# Schematic.net
KiCad netlist of a schematic drawn in Altium Designer
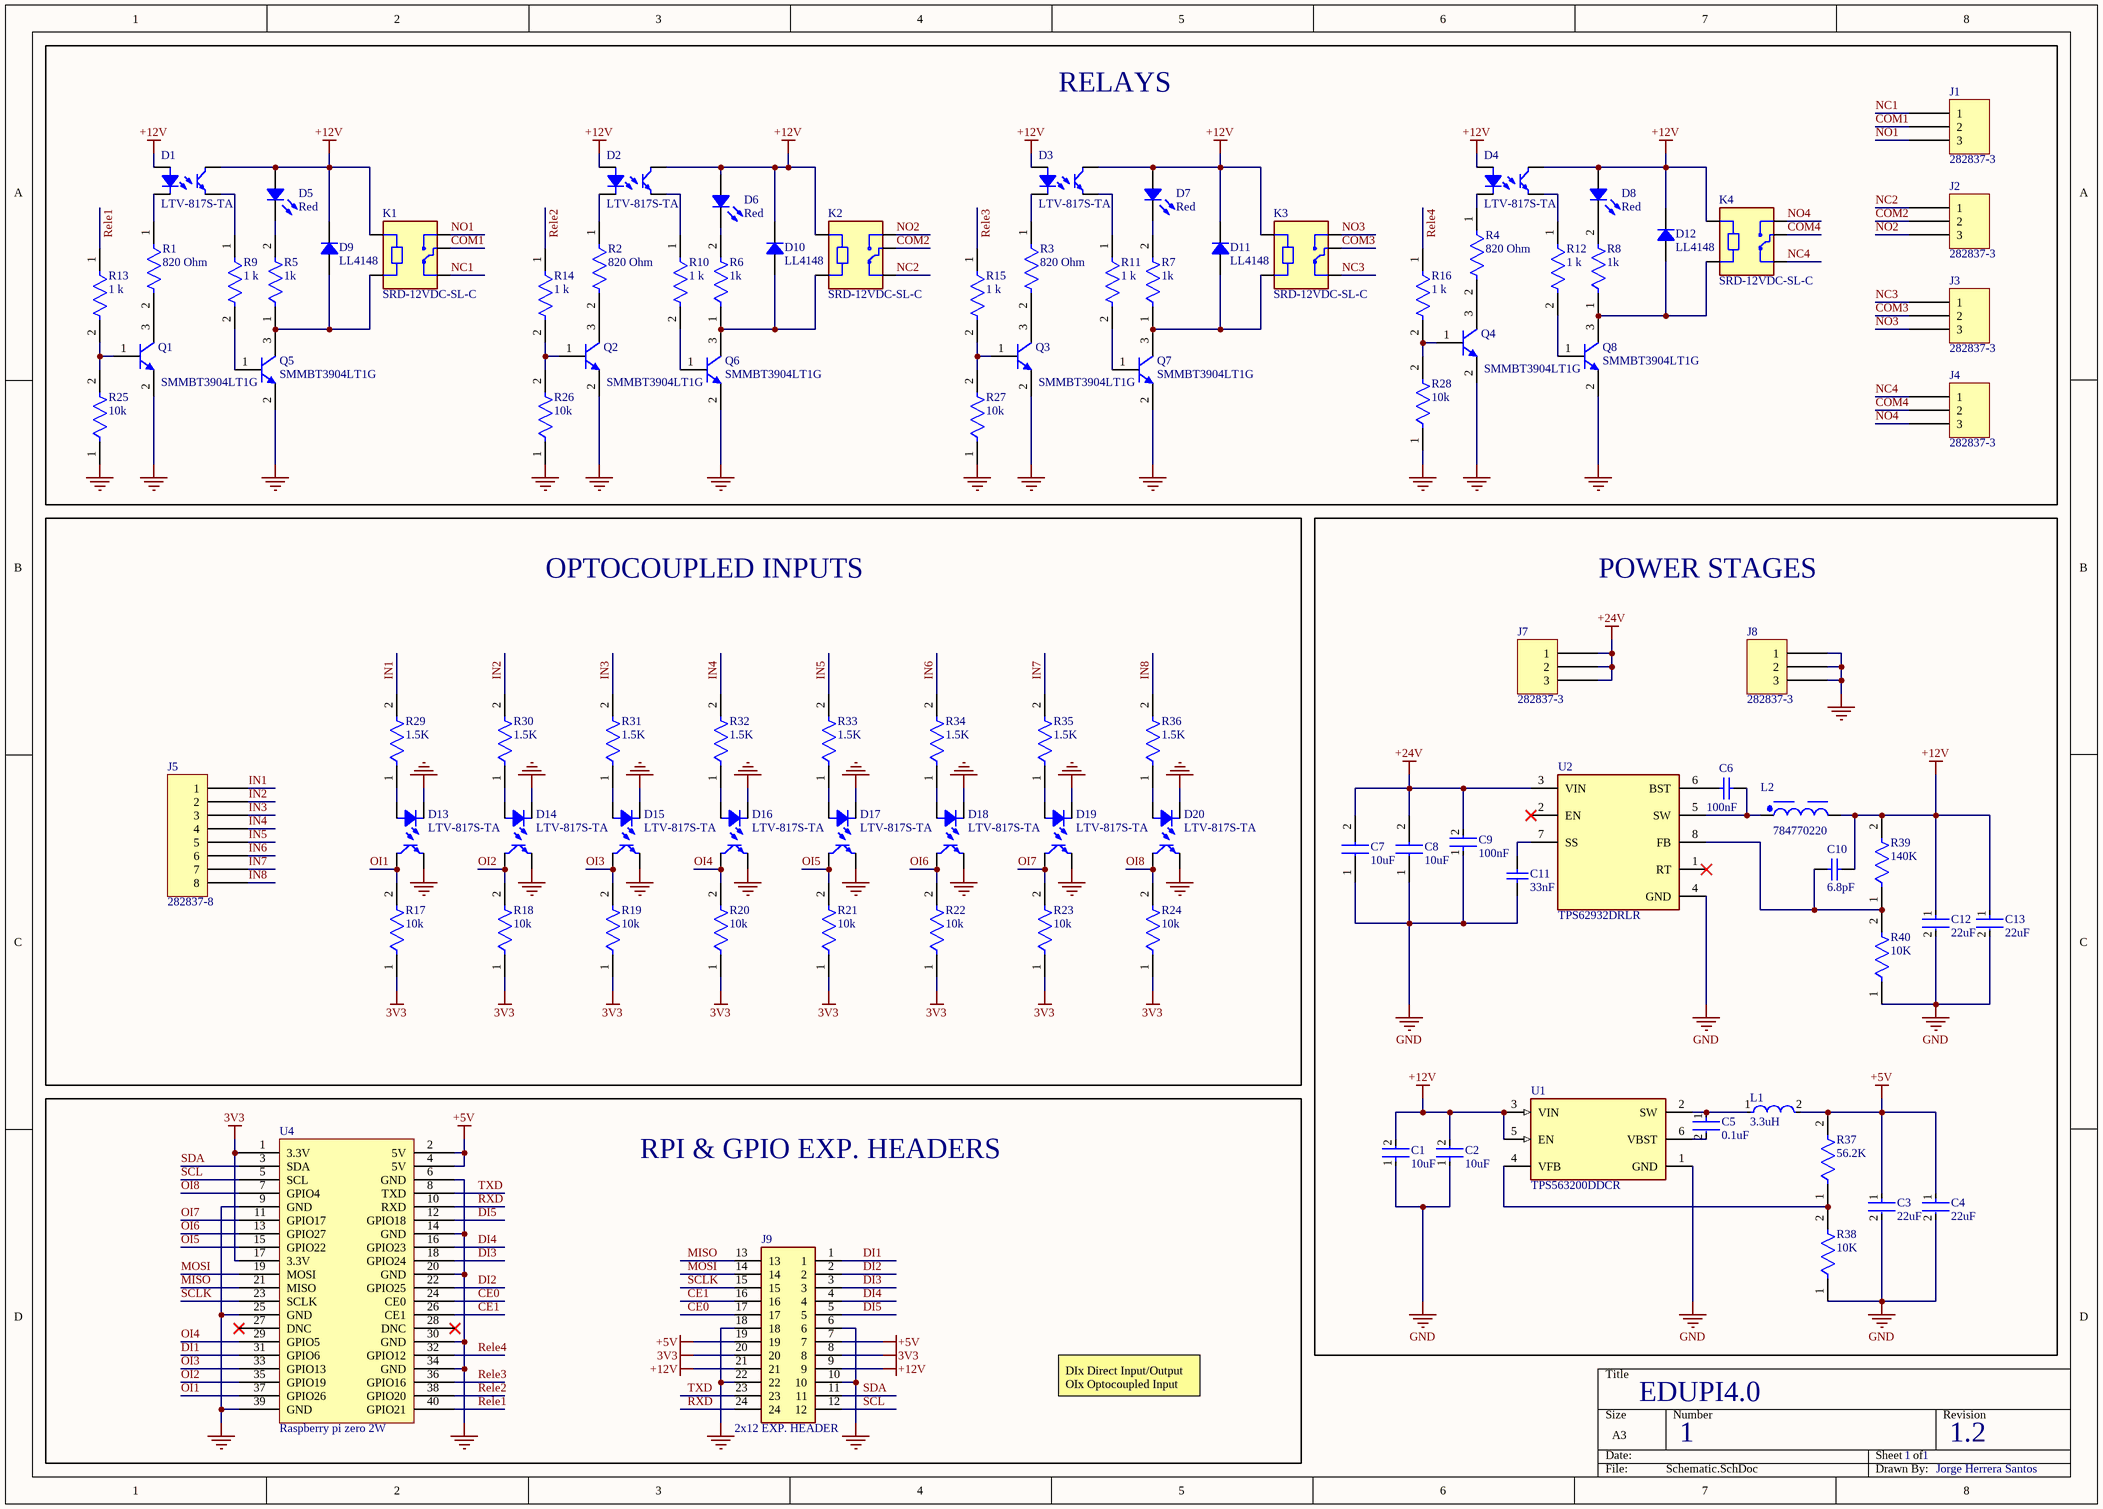
[diagram p0: Schematic.SchDoc]

(export (version "E")
  (design (tool "Eeschema 10.0.6"))
  (components
    (comp (ref "C1")
      (value "10uF")
      (footprint "FP-GRM21B-0_15-IPC_C")
      (description "Chip Multilayer Ceramic Capacitors for General Purpose, 0805, 10uF, X5R, 15%, 10%, 25V")
      (fields (field (name "VOLTAGE") "25V") (field (name "TOLERANCE") "10%"))
      (libsource (lib "Altium Content Vault") (part "b4654b650e69147ec39a6b967a45e02"))
    )
    (comp (ref "C2")
      (value "10uF")
      (footprint "FP-GRM21B-0_15-IPC_C")
      (description "Chip Multilayer Ceramic Capacitors for General Purpose, 0805, 10uF, X5R, 15%, 10%, 25V")
      (fields (field (name "VOLTAGE") "25V") (field (name "TOLERANCE") "10%"))
      (libsource (lib "Altium Content Vault") (part "b4654b650e69147ec39a6b967a45e02"))
    )
    (comp (ref "C3")
      (value "22uF")
      (footprint "FP-GRM21B-0_2-e0_2_0_7-IPC_C")
      (description "Chip Multilayer Ceramic Capacitors for General Purpose, 0805, 22uF, X5R, 15%, 20%, 10V")
      (fields (field (name "TOLERANCE") "20%") (field (name "VOLTAGE") "10V"))
      (libsource (lib "Altium Content Vault") (part "b4654b650e69147ec39a6b967a45e02"))
    )
    (comp (ref "C4")
      (value "22uF")
      (footprint "FP-GRM21B-0_2-e0_2_0_7-IPC_C")
      (description "Chip Multilayer Ceramic Capacitors for General Purpose, 0805, 22uF, X5R, 15%, 20%, 10V")
      (fields (field (name "TOLERANCE") "20%") (field (name "VOLTAGE") "10V"))
      (libsource (lib "Altium Content Vault") (part "b4654b650e69147ec39a6b967a45e02"))
    )
    (comp (ref "C5")
      (value "0.1uF")
      (footprint "FP-CC0805-0_85-MFG")
      (description "CAP CER 0.1UF 25V X7R 0805")
      (fields (field (name "MANUFACTURER PART NUMBER") "CC0805KRX7R8BB104") (field (name "TOLERANCE") "0.1"))
      (libsource (lib "Altium Content Vault") (part "11868f565c42a9108669ba33697ecf6"))
    )
    (comp (ref "C6")
      (value "100nF")
      (footprint "CAPC1005X55X25LL05T10")
      (description "Chip Capacitor, 0.1 uF, +/- 10%, 10 V, -55 to 125 degC, 0402 (1005 Metric), RoHS, Tape and Reel")
      (fields (field (name "MANUFACTURER") "Murata"))
      (libsource (lib "Altium Content Vault") (part "CAP-NP-2"))
    )
    (comp (ref "C7")
      (value "10uF")
      (footprint "CAPC3225X270N")
      (description "Capacitor")
      (fields (field (name "MANUFACTURER_PART_NUMBER") "MSASU32MSB5106KPNA01"))
      (libsource (lib "Raspberry") (part "MSASU32MSB5106KPNA01"))
    )
    (comp (ref "C8")
      (value "10uF")
      (footprint "CAPC3225X270N")
      (description "Capacitor")
      (fields (field (name "MANUFACTURER_PART_NUMBER") "MSASU32MSB5106KPNA01"))
      (libsource (lib "Raspberry") (part "MSASU32MSB5106KPNA01"))
    )
    (comp (ref "C9")
      (value "100nF")
      (footprint "FP-CGA3E-0_3-0_1-IPC_A")
      (description "Cap Ceramic 100nF 50V X7R 10% Pad SMD 0603 +125°C Automotive T/R")
      (fields (field (name "TOLERANCE") "10%") (field (name "VOLTAGE") "50V"))
      (libsource (lib "Altium Content Vault") (part "b4654b650e69147ec39a6b967a45e02"))
    )
    (comp (ref "C10")
      (value "6.8pF")
      (footprint "CAPC1005X55X25NL05T10")
      (fields (field (name "PART NUMBER") "GRM1555C1E6R8CA01D") (field (name "MANUFACTURER") "Murata"))
      (libsource (lib "Altium Content Vault") (part "CAP"))
    )
    (comp (ref "C11")
      (value "33nF")
      (footprint "CAPC1005X55X25NL05T10")
      (fields (field (name "PART NUMBER") "GRM155R71A333KA01D") (field (name "MANUFACTURER") "Murata"))
      (libsource (lib "Altium Content Vault") (part "CAP"))
    )
    (comp (ref "C12")
      (value "22uF")
      (footprint "FP-C3216-160-0_2-IPC_B")
      (description "Multilayer Ceramic Capacitors 22uF ±20% 35V X5R SMD 1206")
      (fields (field (name "TOLERANCE") "20%") (field (name "VOLTAGE") "35V"))
      (libsource (lib "Altium Content Vault") (part "11868f565c42a9108669ba33697ecf6"))
    )
    (comp (ref "C13")
      (value "22uF")
      (footprint "FP-C3216-160-0_2-IPC_B")
      (description "Multilayer Ceramic Capacitors 22uF ±20% 35V X5R SMD 1206")
      (fields (field (name "TOLERANCE") "20%") (field (name "VOLTAGE") "35V"))
      (libsource (lib "Altium Content Vault") (part "11868f565c42a9108669ba33697ecf6"))
    )
    (comp (ref "D1")
      (value "LTV-817S-TA")
      (footprint "LITEON LTV-817")
      (description "OPTOISOLATR 5KV TRANSISTOR 4-SMD")
      (fields (field (name "MANUFACTURER") "Lite-On Inc."))
      (libsource (lib "Celestial Altium Library - altium_library") (part "Optoisolator"))
    )
    (comp (ref "D2")
      (value "LTV-817S-TA")
      (footprint "LITEON LTV-817")
      (description "OPTOISOLATR 5KV TRANSISTOR 4-SMD")
      (fields (field (name "MANUFACTURER") "Lite-On Inc."))
      (libsource (lib "Celestial Altium Library - altium_library") (part "Optoisolator"))
    )
    (comp (ref "D3")
      (value "LTV-817S-TA")
      (footprint "LITEON LTV-817")
      (description "OPTOISOLATR 5KV TRANSISTOR 4-SMD")
      (fields (field (name "MANUFACTURER") "Lite-On Inc."))
      (libsource (lib "Celestial Altium Library - altium_library") (part "Optoisolator"))
    )
    (comp (ref "D4")
      (value "LTV-817S-TA")
      (footprint "LITEON LTV-817")
      (description "OPTOISOLATR 5KV TRANSISTOR 4-SMD")
      (fields (field (name "MANUFACTURER") "Lite-On Inc."))
      (libsource (lib "Celestial Altium Library - altium_library") (part "Optoisolator"))
    )
    (comp (ref "D5")
      (value "Red")
      (footprint "LED 1206_3216 RED")
      (description "LED RED CLEAR SMD")
      (fields (field (name "PART NUMBER") "LTST-C150KAKT") (field (name "MANUFACTURER") "Lite-On Inc."))
      (libsource (lib "Celestial Altium Library - altium_library") (part "LED"))
    )
    (comp (ref "D6")
      (value "Red")
      (footprint "LED 1206_3216 RED")
      (description "LED RED CLEAR SMD")
      (fields (field (name "PART NUMBER") "LTST-C150KAKT") (field (name "MANUFACTURER") "Lite-On Inc."))
      (libsource (lib "Celestial Altium Library - altium_library") (part "LED"))
    )
    (comp (ref "D7")
      (value "Red")
      (footprint "LED 1206_3216 RED")
      (description "LED RED CLEAR SMD")
      (fields (field (name "PART NUMBER") "LTST-C150KAKT") (field (name "MANUFACTURER") "Lite-On Inc."))
      (libsource (lib "Celestial Altium Library - altium_library") (part "LED"))
    )
    (comp (ref "D8")
      (value "Red")
      (footprint "LED 1206_3216 RED")
      (description "LED RED CLEAR SMD")
      (fields (field (name "PART NUMBER") "LTST-C150KAKT") (field (name "MANUFACTURER") "Lite-On Inc."))
      (libsource (lib "Celestial Altium Library - altium_library") (part "LED"))
    )
    (comp (ref "D9")
      (value "LL4148")
      (footprint "SOD-80 MiniMELF")
      (description "DIODE GEN PURP 100V 200MA SOD80")
      (fields (field (name "MANUFACTURER") "ON Semiconductor"))
      (libsource (lib "Celestial Altium Library - altium_library") (part "Diode"))
    )
    (comp (ref "D10")
      (value "LL4148")
      (footprint "SOD-80 MiniMELF")
      (description "DIODE GEN PURP 100V 200MA SOD80")
      (fields (field (name "MANUFACTURER") "ON Semiconductor"))
      (libsource (lib "Celestial Altium Library - altium_library") (part "Diode"))
    )
    (comp (ref "D11")
      (value "LL4148")
      (footprint "SOD-80 MiniMELF")
      (description "DIODE GEN PURP 100V 200MA SOD80")
      (fields (field (name "MANUFACTURER") "ON Semiconductor"))
      (libsource (lib "Celestial Altium Library - altium_library") (part "Diode"))
    )
    (comp (ref "D12")
      (value "LL4148")
      (footprint "SOD-80 MiniMELF")
      (description "DIODE GEN PURP 100V 200MA SOD80")
      (fields (field (name "MANUFACTURER") "ON Semiconductor"))
      (libsource (lib "Celestial Altium Library - altium_library") (part "Diode"))
    )
    (comp (ref "D13")
      (value "LTV-817S-TA")
      (footprint "LITEON LTV-817")
      (description "OPTOISOLATR 5KV TRANSISTOR 4-SMD")
      (fields (field (name "MANUFACTURER") "Lite-On Inc."))
      (libsource (lib "Celestial Altium Library - altium_library") (part "Optoisolator"))
    )
    (comp (ref "D14")
      (value "LTV-817S-TA")
      (footprint "LITEON LTV-817")
      (description "OPTOISOLATR 5KV TRANSISTOR 4-SMD")
      (fields (field (name "MANUFACTURER") "Lite-On Inc."))
      (libsource (lib "Celestial Altium Library - altium_library") (part "Optoisolator"))
    )
    (comp (ref "D15")
      (value "LTV-817S-TA")
      (footprint "LITEON LTV-817")
      (description "OPTOISOLATR 5KV TRANSISTOR 4-SMD")
      (fields (field (name "MANUFACTURER") "Lite-On Inc."))
      (libsource (lib "Celestial Altium Library - altium_library") (part "Optoisolator"))
    )
    (comp (ref "D16")
      (value "LTV-817S-TA")
      (footprint "LITEON LTV-817")
      (description "OPTOISOLATR 5KV TRANSISTOR 4-SMD")
      (fields (field (name "MANUFACTURER") "Lite-On Inc."))
      (libsource (lib "Celestial Altium Library - altium_library") (part "Optoisolator"))
    )
    (comp (ref "D17")
      (value "LTV-817S-TA")
      (footprint "LITEON LTV-817")
      (description "OPTOISOLATR 5KV TRANSISTOR 4-SMD")
      (fields (field (name "MANUFACTURER") "Lite-On Inc."))
      (libsource (lib "Celestial Altium Library - altium_library") (part "Optoisolator"))
    )
    (comp (ref "D18")
      (value "LTV-817S-TA")
      (footprint "LITEON LTV-817")
      (description "OPTOISOLATR 5KV TRANSISTOR 4-SMD")
      (fields (field (name "MANUFACTURER") "Lite-On Inc."))
      (libsource (lib "Celestial Altium Library - altium_library") (part "Optoisolator"))
    )
    (comp (ref "D19")
      (value "LTV-817S-TA")
      (footprint "LITEON LTV-817")
      (description "OPTOISOLATR 5KV TRANSISTOR 4-SMD")
      (fields (field (name "MANUFACTURER") "Lite-On Inc."))
      (libsource (lib "Celestial Altium Library - altium_library") (part "Optoisolator"))
    )
    (comp (ref "D20")
      (value "LTV-817S-TA")
      (footprint "LITEON LTV-817")
      (description "OPTOISOLATR 5KV TRANSISTOR 4-SMD")
      (fields (field (name "MANUFACTURER") "Lite-On Inc."))
      (libsource (lib "Celestial Altium Library - altium_library") (part "Optoisolator"))
    )
    (comp (ref "J1")
      (value "282837-3")
      (footprint "TE 282837-3")
      (description "TERM BLK 3P SIDE ENT 5.08MM PCB")
      (fields (field (name "MANUFACTURER") "TE Connectivity AMP Connectors") (field (name "VOLTAGE") "300 V"))
      (libsource (lib "Celestial Altium Library - altium_library") (part "3 Pin"))
    )
    (comp (ref "J2")
      (value "282837-3")
      (footprint "TE 282837-3")
      (description "TERM BLK 3P SIDE ENT 5.08MM PCB")
      (fields (field (name "MANUFACTURER") "TE Connectivity AMP Connectors") (field (name "VOLTAGE") "300 V"))
      (libsource (lib "Celestial Altium Library - altium_library") (part "3 Pin"))
    )
    (comp (ref "J3")
      (value "282837-3")
      (footprint "TE 282837-3")
      (description "TERM BLK 3P SIDE ENT 5.08MM PCB")
      (fields (field (name "MANUFACTURER") "TE Connectivity AMP Connectors") (field (name "VOLTAGE") "300 V"))
      (libsource (lib "Celestial Altium Library - altium_library") (part "3 Pin"))
    )
    (comp (ref "J4")
      (value "282837-3")
      (footprint "TE 282837-3")
      (description "TERM BLK 3P SIDE ENT 5.08MM PCB")
      (fields (field (name "MANUFACTURER") "TE Connectivity AMP Connectors") (field (name "VOLTAGE") "300 V"))
      (libsource (lib "Celestial Altium Library - altium_library") (part "3 Pin"))
    )
    (comp (ref "J5")
      (value "282837-8")
      (footprint "TE 282837-8")
      (description "TERM BLK 8P SIDE ENT 5.08MM PCB")
      (fields (field (name "MANUFACTURER") "TE Connectivity AMP Connectors") (field (name "VOLTAGE") "300 V"))
      (libsource (lib "Celestial Altium Library - altium_library") (part "8 Pin"))
    )
    (comp (ref "J7")
      (value "282837-3")
      (footprint "TE 282837-3")
      (description "TERM BLK 3P SIDE ENT 5.08MM PCB")
      (fields (field (name "MANUFACTURER") "TE Connectivity AMP Connectors") (field (name "VOLTAGE") "300 V"))
      (libsource (lib "") (part "3 Pin_1"))
    )
    (comp (ref "J8")
      (value "282837-3")
      (footprint "TE 282837-3")
      (description "TERM BLK 3P SIDE ENT 5.08MM PCB")
      (fields (field (name "MANUFACTURER") "TE Connectivity AMP Connectors") (field (name "VOLTAGE") "300 V"))
      (libsource (lib "") (part "3 Pin_1"))
    )
    (comp (ref "J9")
      (value "2x12 EXP. HEADER")
      (footprint "2x12 MALE HEADER")
      (description "Conn Unshrouded Header HDR 20 POS 2.54mm Solder ST Thru-Hole Box")
      (fields (field (name "MF") "TE Connectivity") (field (name "MP") "1-826656-0"))
      (libsource (lib "1-826656-0") (part "2X12 MALE HEADER_1"))
    )
    (comp (ref "K1")
      (value "SRD-12VDC-SL-C")
      (footprint "RELAY_SRD-05VDC-SL-C")
      (fields (field (name "MF") "Songle Relay") (field (name "MP") "SRD-05VDC-SL-C"))
      (libsource (lib "SRD-05VDC-SL-C") (part "SRD-05VDC-SL-C"))
    )
    (comp (ref "K2")
      (value "SRD-12VDC-SL-C")
      (footprint "RELAY_SRD-05VDC-SL-C")
      (fields (field (name "MF") "Songle Relay") (field (name "MP") "SRD-05VDC-SL-C"))
      (libsource (lib "SRD-05VDC-SL-C") (part "SRD-05VDC-SL-C"))
    )
    (comp (ref "K3")
      (value "SRD-12VDC-SL-C")
      (footprint "RELAY_SRD-05VDC-SL-C")
      (fields (field (name "MF") "Songle Relay") (field (name "MP") "SRD-05VDC-SL-C"))
      (libsource (lib "SRD-05VDC-SL-C") (part "SRD-05VDC-SL-C"))
    )
    (comp (ref "K4")
      (value "SRD-12VDC-SL-C")
      (footprint "RELAY_SRD-05VDC-SL-C")
      (fields (field (name "MF") "Songle Relay") (field (name "MP") "SRD-05VDC-SL-C"))
      (libsource (lib "SRD-05VDC-SL-C") (part "SRD-05VDC-SL-C"))
    )
    (comp (ref "L1")
      (value "3.3uH")
      (footprint "FP-NR8040-H_4_2-MFG")
      (description "Shielded Wirewound Inductor 3.3uH 30% 6A 19.5mΩ SMD NRS8040T3R3NJGJ")
      (libsource (lib "Altium Content Vault") (part "725321dda6339637d4d059423bc1c3c"))
    )
    (comp (ref "L2")
      (value "784770220")
      (footprint "WE-PDA_1280")
      (description "Power Inductor, 22Uh, Shielded, 4A Rohs Compliant: Yes")
      (fields (field (name "TOLERANCE") "20%"))
      (libsource (lib "Altium Content Vault") (part "Inductor - 2"))
    )
    (comp (ref "Q1")
      (value "SMMBT3904LT1G")
      (footprint "ONSC-SOT-23-3-318-08_V")
      (description "General Purpose Transistor, NPN Silicon, 3-Pin SOT-23, Pb-Free, Tape and Reel")
      (fields (field (name "MANUFACTURER") "On Semiconductor"))
      (libsource (lib "Altium Content Vault") (part "ONSC-NPN-B1E2C3-3"))
    )
    (comp (ref "Q2")
      (value "SMMBT3904LT1G")
      (footprint "ONSC-SOT-23-3-318-08_V")
      (description "General Purpose Transistor, NPN Silicon, 3-Pin SOT-23, Pb-Free, Tape and Reel")
      (fields (field (name "MANUFACTURER") "On Semiconductor"))
      (libsource (lib "Altium Content Vault") (part "ONSC-NPN-B1E2C3-3"))
    )
    (comp (ref "Q3")
      (value "SMMBT3904LT1G")
      (footprint "ONSC-SOT-23-3-318-08_V")
      (description "General Purpose Transistor, NPN Silicon, 3-Pin SOT-23, Pb-Free, Tape and Reel")
      (fields (field (name "MANUFACTURER") "On Semiconductor"))
      (libsource (lib "Altium Content Vault") (part "ONSC-NPN-B1E2C3-3"))
    )
    (comp (ref "Q4")
      (value "SMMBT3904LT1G")
      (footprint "ONSC-SOT-23-3-318-08_V")
      (description "General Purpose Transistor, NPN Silicon, 3-Pin SOT-23, Pb-Free, Tape and Reel")
      (fields (field (name "MANUFACTURER") "On Semiconductor"))
      (libsource (lib "Altium Content Vault") (part "ONSC-NPN-B1E2C3-3"))
    )
    (comp (ref "Q5")
      (value "SMMBT3904LT1G")
      (footprint "ONSC-SOT-23-3-318-08_V")
      (description "General Purpose Transistor, NPN Silicon, 3-Pin SOT-23, Pb-Free, Tape and Reel")
      (fields (field (name "MANUFACTURER") "On Semiconductor"))
      (libsource (lib "Altium Content Vault") (part "ONSC-NPN-B1E2C3-3"))
    )
    (comp (ref "Q6")
      (value "SMMBT3904LT1G")
      (footprint "ONSC-SOT-23-3-318-08_V")
      (description "General Purpose Transistor, NPN Silicon, 3-Pin SOT-23, Pb-Free, Tape and Reel")
      (fields (field (name "MANUFACTURER") "On Semiconductor"))
      (libsource (lib "Altium Content Vault") (part "ONSC-NPN-B1E2C3-3"))
    )
    (comp (ref "Q7")
      (value "SMMBT3904LT1G")
      (footprint "ONSC-SOT-23-3-318-08_V")
      (description "General Purpose Transistor, NPN Silicon, 3-Pin SOT-23, Pb-Free, Tape and Reel")
      (fields (field (name "MANUFACTURER") "On Semiconductor"))
      (libsource (lib "Altium Content Vault") (part "ONSC-NPN-B1E2C3-3"))
    )
    (comp (ref "Q8")
      (value "SMMBT3904LT1G")
      (footprint "ONSC-SOT-23-3-318-08_V")
      (description "General Purpose Transistor, NPN Silicon, 3-Pin SOT-23, Pb-Free, Tape and Reel")
      (fields (field (name "MANUFACTURER") "On Semiconductor"))
      (libsource (lib "Altium Content Vault") (part "ONSC-NPN-B1E2C3-3"))
    )
    (comp (ref "R1")
      (value "820 Ohm")
      (footprint "FP-CRCW0603-HPe3-MFG")
      (description "RES Thick Film, 820Ω, 1%, 0.33W, 100ppm/°C, 0603")
      (fields (field (name "TOLERANCE") "1%"))
      (libsource (lib "Altium Content Vault") (part "1029c3af85768c4190bb7ad29bc67b5"))
    )
    (comp (ref "R2")
      (value "820 Ohm")
      (footprint "FP-CRCW0603-HPe3-MFG")
      (description "RES Thick Film, 820Ω, 1%, 0.33W, 100ppm/°C, 0603")
      (fields (field (name "TOLERANCE") "1%"))
      (libsource (lib "Altium Content Vault") (part "1029c3af85768c4190bb7ad29bc67b5"))
    )
    (comp (ref "R3")
      (value "820 Ohm")
      (footprint "FP-CRCW0603-HPe3-MFG")
      (description "RES Thick Film, 820Ω, 1%, 0.33W, 100ppm/°C, 0603")
      (fields (field (name "TOLERANCE") "1%"))
      (libsource (lib "Altium Content Vault") (part "1029c3af85768c4190bb7ad29bc67b5"))
    )
    (comp (ref "R4")
      (value "820 Ohm")
      (footprint "FP-CRCW0603-HPe3-MFG")
      (description "RES Thick Film, 820Ω, 1%, 0.33W, 100ppm/°C, 0603")
      (fields (field (name "TOLERANCE") "1%"))
      (libsource (lib "Altium Content Vault") (part "1029c3af85768c4190bb7ad29bc67b5"))
    )
    (comp (ref "R5")
      (value "1k")
      (footprint "FP-CRCW0603-HPe3-MFG")
      (description "RES Thick Film, 820Ω, 1%, 0.33W, 100ppm/°C, 0603")
      (fields (field (name "TOLERANCE") "1%"))
      (libsource (lib "Altium Content Vault") (part "1029c3af85768c4190bb7ad29bc67b5"))
    )
    (comp (ref "R6")
      (value "1k")
      (footprint "FP-CRCW0603-HPe3-MFG")
      (description "RES Thick Film, 820Ω, 1%, 0.33W, 100ppm/°C, 0603")
      (fields (field (name "TOLERANCE") "1%"))
      (libsource (lib "Altium Content Vault") (part "1029c3af85768c4190bb7ad29bc67b5"))
    )
    (comp (ref "R7")
      (value "1k")
      (footprint "FP-CRCW0603-HPe3-MFG")
      (description "RES Thick Film, 820Ω, 1%, 0.33W, 100ppm/°C, 0603")
      (fields (field (name "TOLERANCE") "1%"))
      (libsource (lib "Altium Content Vault") (part "1029c3af85768c4190bb7ad29bc67b5"))
    )
    (comp (ref "R8")
      (value "1k")
      (footprint "FP-CRCW0603-HPe3-MFG")
      (description "RES Thick Film, 820Ω, 1%, 0.33W, 100ppm/°C, 0603")
      (fields (field (name "TOLERANCE") "1%"))
      (libsource (lib "Altium Content Vault") (part "1029c3af85768c4190bb7ad29bc67b5"))
    )
    (comp (ref "R9")
      (value "1 k")
      (footprint "FP-MCT0603-IPC_C")
      (description "MCT0603PD1001DP500 RES SMD 100 OHM 1% 1/8W 0603")
      (fields (field (name "TOLERANCE") "0.5%"))
      (libsource (lib "Altium Content Vault") (part "1029c3af85768c4190bb7ad29bc67b5"))
    )
    (comp (ref "R10")
      (value "1 k")
      (footprint "FP-MCT0603-IPC_C")
      (description "MCT0603PD1001DP500 RES SMD 100 OHM 1% 1/8W 0603")
      (fields (field (name "TOLERANCE") "0.5%"))
      (libsource (lib "Altium Content Vault") (part "1029c3af85768c4190bb7ad29bc67b5"))
    )
    (comp (ref "R11")
      (value "1 k")
      (footprint "FP-MCT0603-IPC_C")
      (description "MCT0603PD1001DP500 RES SMD 100 OHM 1% 1/8W 0603")
      (fields (field (name "TOLERANCE") "0.5%"))
      (libsource (lib "Altium Content Vault") (part "1029c3af85768c4190bb7ad29bc67b5"))
    )
    (comp (ref "R12")
      (value "1 k")
      (footprint "FP-MCT0603-IPC_C")
      (description "MCT0603PD1001DP500 RES SMD 100 OHM 1% 1/8W 0603")
      (fields (field (name "TOLERANCE") "0.5%"))
      (libsource (lib "Altium Content Vault") (part "1029c3af85768c4190bb7ad29bc67b5"))
    )
    (comp (ref "R13")
      (value "1 k")
      (footprint "FP-MCT0603-IPC_C")
      (description "MCT0603PD1001DP500 RES SMD 100 OHM 1% 1/8W 0603")
      (fields (field (name "TOLERANCE") "0.5%"))
      (libsource (lib "Altium Content Vault") (part "1029c3af85768c4190bb7ad29bc67b5"))
    )
    (comp (ref "R14")
      (value "1 k")
      (footprint "FP-MCT0603-IPC_C")
      (description "MCT0603PD1001DP500 RES SMD 100 OHM 1% 1/8W 0603")
      (fields (field (name "TOLERANCE") "0.5%"))
      (libsource (lib "Altium Content Vault") (part "1029c3af85768c4190bb7ad29bc67b5"))
    )
    (comp (ref "R15")
      (value "1 k")
      (footprint "FP-MCT0603-IPC_C")
      (description "MCT0603PD1001DP500 RES SMD 100 OHM 1% 1/8W 0603")
      (fields (field (name "TOLERANCE") "0.5%"))
      (libsource (lib "Altium Content Vault") (part "1029c3af85768c4190bb7ad29bc67b5"))
    )
    (comp (ref "R16")
      (value "1 k")
      (footprint "FP-MCT0603-IPC_C")
      (description "MCT0603PD1001DP500 RES SMD 100 OHM 1% 1/8W 0603")
      (fields (field (name "TOLERANCE") "0.5%"))
      (libsource (lib "Altium Content Vault") (part "1029c3af85768c4190bb7ad29bc67b5"))
    )
    (comp (ref "R17")
      (value "10k")
      (footprint "FP-MCT0603-IPC_B")
      (description "MCT0603MD1002BP100 RES SMD 10k OHM 1% 1/8W 0603")
      (fields (field (name "TOLERANCE") "0.1%"))
      (libsource (lib "Altium Content Vault") (part "1029c3af85768c4190bb7ad29bc67b5"))
    )
    (comp (ref "R18")
      (value "10k")
      (footprint "FP-MCT0603-IPC_B")
      (description "MCT0603MD1002BP100 RES SMD 10k OHM 1% 1/8W 0603")
      (fields (field (name "TOLERANCE") "0.1%"))
      (libsource (lib "Altium Content Vault") (part "1029c3af85768c4190bb7ad29bc67b5"))
    )
    (comp (ref "R19")
      (value "10k")
      (footprint "FP-MCT0603-IPC_B")
      (description "MCT0603MD1002BP100 RES SMD 10k OHM 1% 1/8W 0603")
      (fields (field (name "TOLERANCE") "0.1%"))
      (libsource (lib "Altium Content Vault") (part "1029c3af85768c4190bb7ad29bc67b5"))
    )
    (comp (ref "R20")
      (value "10k")
      (footprint "FP-MCT0603-IPC_B")
      (description "MCT0603MD1002BP100 RES SMD 10k OHM 1% 1/8W 0603")
      (fields (field (name "TOLERANCE") "0.1%"))
      (libsource (lib "Altium Content Vault") (part "1029c3af85768c4190bb7ad29bc67b5"))
    )
    (comp (ref "R21")
      (value "10k")
      (footprint "FP-MCT0603-IPC_B")
      (description "MCT0603MD1002BP100 RES SMD 10k OHM 1% 1/8W 0603")
      (fields (field (name "TOLERANCE") "0.1%"))
      (libsource (lib "Altium Content Vault") (part "1029c3af85768c4190bb7ad29bc67b5"))
    )
    (comp (ref "R22")
      (value "10k")
      (footprint "FP-MCT0603-IPC_B")
      (description "MCT0603MD1002BP100 RES SMD 10k OHM 1% 1/8W 0603")
      (fields (field (name "TOLERANCE") "0.1%"))
      (libsource (lib "Altium Content Vault") (part "1029c3af85768c4190bb7ad29bc67b5"))
    )
    (comp (ref "R23")
      (value "10k")
      (footprint "FP-MCT0603-IPC_B")
      (description "MCT0603MD1002BP100 RES SMD 10k OHM 1% 1/8W 0603")
      (fields (field (name "TOLERANCE") "0.1%"))
      (libsource (lib "Altium Content Vault") (part "1029c3af85768c4190bb7ad29bc67b5"))
    )
    (comp (ref "R24")
      (value "10k")
      (footprint "FP-MCT0603-IPC_B")
      (description "MCT0603MD1002BP100 RES SMD 10k OHM 1% 1/8W 0603")
      (fields (field (name "TOLERANCE") "0.1%"))
      (libsource (lib "Altium Content Vault") (part "1029c3af85768c4190bb7ad29bc67b5"))
    )
    (comp (ref "R25")
      (value "10k")
      (footprint "FP-MCT0603-IPC_B")
      (description "MCT0603MD1002BP100 RES SMD 10k OHM 1% 1/8W 0603")
      (fields (field (name "TOLERANCE") "0.1%"))
      (libsource (lib "Altium Content Vault") (part "1029c3af85768c4190bb7ad29bc67b5"))
    )
    (comp (ref "R26")
      (value "10k")
      (footprint "FP-MCT0603-IPC_B")
      (description "MCT0603MD1002BP100 RES SMD 10k OHM 1% 1/8W 0603")
      (fields (field (name "TOLERANCE") "0.1%"))
      (libsource (lib "Altium Content Vault") (part "1029c3af85768c4190bb7ad29bc67b5"))
    )
    (comp (ref "R27")
      (value "10k")
      (footprint "FP-MCT0603-IPC_B")
      (description "MCT0603MD1002BP100 RES SMD 10k OHM 1% 1/8W 0603")
      (fields (field (name "TOLERANCE") "0.1%"))
      (libsource (lib "Altium Content Vault") (part "1029c3af85768c4190bb7ad29bc67b5"))
    )
    (comp (ref "R28")
      (value "10k")
      (footprint "FP-MCT0603-IPC_B")
      (description "MCT0603MD1002BP100 RES SMD 10k OHM 1% 1/8W 0603")
      (fields (field (name "TOLERANCE") "0.1%"))
      (libsource (lib "Altium Content Vault") (part "1029c3af85768c4190bb7ad29bc67b5"))
    )
    (comp (ref "R29")
      (value "1.5K")
      (footprint "FP-CRCW0603-e3-IPC_C")
      (description "CRCW06031K50FKEC RES Thick Film, 1.5kΩ, 1%, 0.1W, 100ppm/°C, 0603")
      (fields (field (name "TOLERANCE") "1%"))
      (libsource (lib "Altium Content Vault") (part "1029c3af85768c4190bb7ad29bc67b5"))
    )
    (comp (ref "R30")
      (value "1.5K")
      (footprint "FP-CRCW0603-e3-IPC_C")
      (description "CRCW06031K50FKEC RES Thick Film, 1.5kΩ, 1%, 0.1W, 100ppm/°C, 0603")
      (fields (field (name "TOLERANCE") "1%"))
      (libsource (lib "Altium Content Vault") (part "1029c3af85768c4190bb7ad29bc67b5"))
    )
    (comp (ref "R31")
      (value "1.5K")
      (footprint "FP-CRCW0603-e3-IPC_C")
      (description "CRCW06031K50FKEC RES Thick Film, 1.5kΩ, 1%, 0.1W, 100ppm/°C, 0603")
      (fields (field (name "TOLERANCE") "1%"))
      (libsource (lib "Altium Content Vault") (part "1029c3af85768c4190bb7ad29bc67b5"))
    )
    (comp (ref "R32")
      (value "1.5K")
      (footprint "FP-CRCW0603-e3-IPC_C")
      (description "CRCW06031K50FKEC RES Thick Film, 1.5kΩ, 1%, 0.1W, 100ppm/°C, 0603")
      (fields (field (name "TOLERANCE") "1%"))
      (libsource (lib "Altium Content Vault") (part "1029c3af85768c4190bb7ad29bc67b5"))
    )
    (comp (ref "R33")
      (value "1.5K")
      (footprint "FP-CRCW0603-e3-IPC_C")
      (description "CRCW06031K50FKEC RES Thick Film, 1.5kΩ, 1%, 0.1W, 100ppm/°C, 0603")
      (fields (field (name "TOLERANCE") "1%"))
      (libsource (lib "Altium Content Vault") (part "1029c3af85768c4190bb7ad29bc67b5"))
    )
    (comp (ref "R34")
      (value "1.5K")
      (footprint "FP-CRCW0603-e3-IPC_C")
      (description "CRCW06031K50FKEC RES Thick Film, 1.5kΩ, 1%, 0.1W, 100ppm/°C, 0603")
      (fields (field (name "TOLERANCE") "1%"))
      (libsource (lib "Altium Content Vault") (part "1029c3af85768c4190bb7ad29bc67b5"))
    )
    (comp (ref "R35")
      (value "1.5K")
      (footprint "FP-CRCW0603-e3-IPC_C")
      (description "CRCW06031K50FKEC RES Thick Film, 1.5kΩ, 1%, 0.1W, 100ppm/°C, 0603")
      (fields (field (name "TOLERANCE") "1%"))
      (libsource (lib "Altium Content Vault") (part "1029c3af85768c4190bb7ad29bc67b5"))
    )
    (comp (ref "R36")
      (value "1.5K")
      (footprint "FP-CRCW0603-e3-IPC_C")
      (description "CRCW06031K50FKEC RES Thick Film, 1.5kΩ, 1%, 0.1W, 100ppm/°C, 0603")
      (fields (field (name "TOLERANCE") "1%"))
      (libsource (lib "Altium Content Vault") (part "1029c3af85768c4190bb7ad29bc67b5"))
    )
    (comp (ref "R37")
      (value "56.2K")
      (footprint "FP-MCT0603-IPC_B")
      (description "RES SMD 100 OHM 1% 1/8W 0603")
      (fields (field (name "TOLERANCE") "1%"))
      (libsource (lib "Altium Content Vault") (part "1029c3af85768c4190bb7ad29bc67b5"))
    )
    (comp (ref "R38")
      (value "10K")
      (footprint "FP-MCT0603-IPC_C")
      (description "RES SMD 10K OHM 1% 1/8W 0603")
      (fields (field (name "TOLERANCE") "1%"))
      (libsource (lib "Altium Content Vault") (part "1029c3af85768c4190bb7ad29bc67b5"))
    )
    (comp (ref "R39")
      (value "140K")
      (footprint "FP-CRCW0603-HPe3-IPC_C")
      (description "RES Thick Film, 140kΩ, 1%, 0.33W, 100ppm/°C, 0603")
      (fields (field (name "TOLERANCE") "1%"))
      (libsource (lib "Altium Content Vault") (part "1029c3af85768c4190bb7ad29bc67b5"))
    )
    (comp (ref "R40")
      (value "10K")
      (footprint "FP-MCT0603-IPC_C")
      (description "RES SMD 10K OHM 1% 1/5W 0603")
      (fields (field (name "TOLERANCE") "1%"))
      (libsource (lib "Altium Content Vault") (part "1029c3af85768c4190bb7ad29bc67b5"))
    )
    (comp (ref "U1")
      (value "TPS563200DDCR")
      (footprint "FP-DDC0006A-MFG")
      (description "IC REG BUCK ADJ 3A TSOT23-6")
      (libsource (lib "Altium Content Vault") (part "31d0a13bcb823f7fa58c78a9b473f81"))
    )
    (comp (ref "U2")
      (value "TPS62932DRLR")
      (footprint "FP-DRL0008A-MFG")
      (description "3.8-V TO 30-V INPUT, 2-A, 200-KH")
      (libsource (lib "Altium Content Vault") (part "530d7937587d685a4b43e131d046c77"))
    )
    (comp (ref "U4")
      (value "Raspberry pi zero 2W")
      (footprint "Raspberry Pi Zero 2 W")
      (libsource (lib "Raspberry") (part "Raspberry pi zero 2W"))
    )
  )
  (nets
    (net (code "1") (name "+5V") (class "Default")
      (node (ref "C3") (pin "1") (pinfunction "1_1") (pintype "passive"))
      (node (ref "C4") (pin "1") (pinfunction "1_1") (pintype "passive"))
      (node (ref "J9") (pin "19") (pinfunction "19_19") (pintype "passive"))
      (node (ref "J9") (pin "7") (pinfunction "7_7") (pintype "passive"))
      (node (ref "L1") (pin "2") (pinfunction "2_2") (pintype "passive"))
      (node (ref "R37") (pin "2") (pinfunction "2_2") (pintype "passive"))
      (node (ref "U4") (pin "2") (pinfunction "5V_2") (pintype "passive"))
      (node (ref "U4") (pin "4") (pinfunction "5V_4") (pintype "passive"))
    )
    (net (code "2") (name "+12V") (class "Default")
      (node (ref "C1") (pin "2") (pinfunction "2_2") (pintype "passive"))
      (node (ref "C10") (pin "2") (pinfunction "2_2") (pintype "passive"))
      (node (ref "C12") (pin "1") (pinfunction "1_1") (pintype "passive"))
      (node (ref "C13") (pin "1") (pinfunction "1_1") (pintype "passive"))
      (node (ref "C2") (pin "2") (pinfunction "2_2") (pintype "passive"))
      (node (ref "D1") (pin "1") (pinfunction "1_1") (pintype "passive"))
      (node (ref "D1") (pin "4") (pinfunction "4_4") (pintype "passive"))
      (node (ref "D10") (pin "2") (pinfunction "2_2") (pintype "passive"))
      (node (ref "D11") (pin "2") (pinfunction "2_2") (pintype "passive"))
      (node (ref "D12") (pin "2") (pinfunction "2_2") (pintype "passive"))
      (node (ref "D2") (pin "1") (pinfunction "1_1") (pintype "passive"))
      (node (ref "D2") (pin "4") (pinfunction "4_4") (pintype "passive"))
      (node (ref "D3") (pin "1") (pinfunction "1_1") (pintype "passive"))
      (node (ref "D3") (pin "4") (pinfunction "4_4") (pintype "passive"))
      (node (ref "D4") (pin "1") (pinfunction "1_1") (pintype "passive"))
      (node (ref "D4") (pin "4") (pinfunction "4_4") (pintype "passive"))
      (node (ref "D5") (pin "1") (pinfunction "1_1") (pintype "passive"))
      (node (ref "D6") (pin "1") (pinfunction "1_1") (pintype "passive"))
      (node (ref "D7") (pin "1") (pinfunction "1_1") (pintype "passive"))
      (node (ref "D8") (pin "1") (pinfunction "1_1") (pintype "passive"))
      (node (ref "D9") (pin "2") (pinfunction "2_2") (pintype "passive"))
      (node (ref "J9") (pin "21") (pinfunction "21_21") (pintype "passive"))
      (node (ref "J9") (pin "9") (pinfunction "9_9") (pintype "passive"))
      (node (ref "K1") (pin "A1") (pinfunction "A1_A1") (pintype "passive"))
      (node (ref "K2") (pin "A1") (pinfunction "A1_A1") (pintype "passive"))
      (node (ref "K3") (pin "A1") (pinfunction "A1_A1") (pintype "passive"))
      (node (ref "K4") (pin "A1") (pinfunction "A1_A1") (pintype "passive"))
      (node (ref "L2") (pin "2") (pinfunction "2_2") (pintype "passive"))
      (node (ref "R39") (pin "2") (pinfunction "2_2") (pintype "passive"))
      (node (ref "U1") (pin "3") (pinfunction "VIN_3") (pintype "input"))
      (node (ref "U1") (pin "5") (pinfunction "EN_5") (pintype "input"))
    )
    (net (code "3") (name "+24V") (class "Default")
      (node (ref "C7") (pin "2") (pinfunction "2_2") (pintype "passive"))
      (node (ref "C8") (pin "2") (pinfunction "2_2") (pintype "passive"))
      (node (ref "C9") (pin "2") (pinfunction "2_2") (pintype "passive"))
      (node (ref "J7") (pin "1") (pinfunction "1_1") (pintype "passive"))
      (node (ref "J7") (pin "2") (pinfunction "2_2") (pintype "passive"))
      (node (ref "J7") (pin "3") (pinfunction "3_3") (pintype "passive"))
      (node (ref "U2") (pin "3") (pinfunction "VIN_3") (pintype "power_in"))
    )
    (net (code "4") (name "/CE0") (class "Default")
      (node (ref "J9") (pin "17") (pinfunction "17_17") (pintype "passive"))
      (node (ref "U4") (pin "24") (pinfunction "CE0_24") (pintype "passive"))
    )
    (net (code "5") (name "/CE1") (class "Default")
      (node (ref "J9") (pin "16") (pinfunction "16_16") (pintype "passive"))
      (node (ref "U4") (pin "26") (pinfunction "CE1_26") (pintype "passive"))
    )
    (net (code "6") (name "/COM1") (class "Default")
      (node (ref "J1") (pin "2") (pinfunction "2_2") (pintype "passive"))
      (node (ref "K1") (pin "COM") (pinfunction "COM_COM") (pintype "passive"))
    )
    (net (code "7") (name "/COM2") (class "Default")
      (node (ref "J2") (pin "2") (pinfunction "2_2") (pintype "passive"))
      (node (ref "K2") (pin "COM") (pinfunction "COM_COM") (pintype "passive"))
    )
    (net (code "8") (name "/COM3") (class "Default")
      (node (ref "J3") (pin "2") (pinfunction "2_2") (pintype "passive"))
      (node (ref "K3") (pin "COM") (pinfunction "COM_COM") (pintype "passive"))
    )
    (net (code "9") (name "/COM4") (class "Default")
      (node (ref "J4") (pin "2") (pinfunction "2_2") (pintype "passive"))
      (node (ref "K4") (pin "COM") (pinfunction "COM_COM") (pintype "passive"))
    )
    (net (code "10") (name "/DI1") (class "Default")
      (node (ref "J9") (pin "1") (pinfunction "1_1") (pintype "passive"))
      (node (ref "U4") (pin "31") (pinfunction "GPIO6_31") (pintype "passive"))
    )
    (net (code "11") (name "/DI2") (class "Default")
      (node (ref "J9") (pin "2") (pinfunction "2_2") (pintype "passive"))
      (node (ref "U4") (pin "22") (pinfunction "GPIO25_22") (pintype "passive"))
    )
    (net (code "12") (name "/DI3") (class "Default")
      (node (ref "J9") (pin "3") (pinfunction "3_3") (pintype "passive"))
      (node (ref "U4") (pin "18") (pinfunction "GPIO24_18") (pintype "passive"))
    )
    (net (code "13") (name "/DI4") (class "Default")
      (node (ref "J9") (pin "4") (pinfunction "4_4") (pintype "passive"))
      (node (ref "U4") (pin "16") (pinfunction "GPIO23_16") (pintype "passive"))
    )
    (net (code "14") (name "/DI5") (class "Default")
      (node (ref "J9") (pin "5") (pinfunction "5_5") (pintype "passive"))
      (node (ref "U4") (pin "12") (pinfunction "GPIO18_12") (pintype "passive"))
    )
    (net (code "15") (name "/IN1") (class "Default")
      (node (ref "J5") (pin "1") (pinfunction "1_1") (pintype "passive"))
      (node (ref "R29") (pin "2") (pinfunction "2_2") (pintype "passive"))
    )
    (net (code "16") (name "/IN2") (class "Default")
      (node (ref "J5") (pin "2") (pinfunction "2_2") (pintype "passive"))
      (node (ref "R30") (pin "2") (pinfunction "2_2") (pintype "passive"))
    )
    (net (code "17") (name "/IN3") (class "Default")
      (node (ref "J5") (pin "3") (pinfunction "3_3") (pintype "passive"))
      (node (ref "R31") (pin "2") (pinfunction "2_2") (pintype "passive"))
    )
    (net (code "18") (name "/IN4") (class "Default")
      (node (ref "J5") (pin "4") (pinfunction "4_4") (pintype "passive"))
      (node (ref "R32") (pin "2") (pinfunction "2_2") (pintype "passive"))
    )
    (net (code "19") (name "/IN5") (class "Default")
      (node (ref "J5") (pin "5") (pinfunction "5_5") (pintype "passive"))
      (node (ref "R33") (pin "2") (pinfunction "2_2") (pintype "passive"))
    )
    (net (code "20") (name "/IN6") (class "Default")
      (node (ref "J5") (pin "6") (pinfunction "6_6") (pintype "passive"))
      (node (ref "R34") (pin "2") (pinfunction "2_2") (pintype "passive"))
    )
    (net (code "21") (name "/IN7") (class "Default")
      (node (ref "J5") (pin "7") (pinfunction "7_7") (pintype "passive"))
      (node (ref "R35") (pin "2") (pinfunction "2_2") (pintype "passive"))
    )
    (net (code "22") (name "/IN8") (class "Default")
      (node (ref "J5") (pin "8") (pinfunction "8_8") (pintype "passive"))
      (node (ref "R36") (pin "2") (pinfunction "2_2") (pintype "passive"))
    )
    (net (code "23") (name "/MISO") (class "Default")
      (node (ref "J9") (pin "13") (pinfunction "13_13") (pintype "passive"))
      (node (ref "U4") (pin "21") (pinfunction "MISO_21") (pintype "passive"))
    )
    (net (code "24") (name "/MOSI") (class "Default")
      (node (ref "J9") (pin "14") (pinfunction "14_14") (pintype "passive"))
      (node (ref "U4") (pin "19") (pinfunction "MOSI_19") (pintype "passive"))
    )
    (net (code "25") (name "/NC1") (class "Default")
      (node (ref "J1") (pin "1") (pinfunction "1_1") (pintype "passive"))
      (node (ref "K1") (pin "NC") (pinfunction "NC_NC") (pintype "passive"))
    )
    (net (code "26") (name "/NC2") (class "Default")
      (node (ref "J2") (pin "1") (pinfunction "1_1") (pintype "passive"))
      (node (ref "K2") (pin "NC") (pinfunction "NC_NC") (pintype "passive"))
    )
    (net (code "27") (name "/NC3") (class "Default")
      (node (ref "J3") (pin "1") (pinfunction "1_1") (pintype "passive"))
      (node (ref "K3") (pin "NC") (pinfunction "NC_NC") (pintype "passive"))
    )
    (net (code "28") (name "/NC4") (class "Default")
      (node (ref "J4") (pin "1") (pinfunction "1_1") (pintype "passive"))
      (node (ref "K4") (pin "NC") (pinfunction "NC_NC") (pintype "passive"))
    )
    (net (code "29") (name "/NO1") (class "Default")
      (node (ref "J1") (pin "3") (pinfunction "3_3") (pintype "passive"))
      (node (ref "K1") (pin "NO") (pinfunction "NO_NO") (pintype "passive"))
    )
    (net (code "30") (name "/NO2") (class "Default")
      (node (ref "J2") (pin "3") (pinfunction "3_3") (pintype "passive"))
      (node (ref "K2") (pin "NO") (pinfunction "NO_NO") (pintype "passive"))
    )
    (net (code "31") (name "/NO3") (class "Default")
      (node (ref "J3") (pin "3") (pinfunction "3_3") (pintype "passive"))
      (node (ref "K3") (pin "NO") (pinfunction "NO_NO") (pintype "passive"))
    )
    (net (code "32") (name "/NO4") (class "Default")
      (node (ref "J4") (pin "3") (pinfunction "3_3") (pintype "passive"))
      (node (ref "K4") (pin "NO") (pinfunction "NO_NO") (pintype "passive"))
    )
    (net (code "33") (name "/OI1") (class "Default")
      (node (ref "D13") (pin "4") (pinfunction "4_4") (pintype "passive"))
      (node (ref "R17") (pin "2") (pinfunction "2_2") (pintype "passive"))
      (node (ref "U4") (pin "37") (pinfunction "GPIO26_37") (pintype "passive"))
    )
    (net (code "34") (name "/OI2") (class "Default")
      (node (ref "D14") (pin "4") (pinfunction "4_4") (pintype "passive"))
      (node (ref "R18") (pin "2") (pinfunction "2_2") (pintype "passive"))
      (node (ref "U4") (pin "35") (pinfunction "GPIO19_35") (pintype "passive"))
    )
    (net (code "35") (name "/OI3") (class "Default")
      (node (ref "D15") (pin "4") (pinfunction "4_4") (pintype "passive"))
      (node (ref "R19") (pin "2") (pinfunction "2_2") (pintype "passive"))
      (node (ref "U4") (pin "33") (pinfunction "GPIO13_33") (pintype "passive"))
    )
    (net (code "36") (name "/OI4") (class "Default")
      (node (ref "D16") (pin "4") (pinfunction "4_4") (pintype "passive"))
      (node (ref "R20") (pin "2") (pinfunction "2_2") (pintype "passive"))
      (node (ref "U4") (pin "29") (pinfunction "GPIO5_29") (pintype "passive"))
    )
    (net (code "37") (name "/OI5") (class "Default")
      (node (ref "D17") (pin "4") (pinfunction "4_4") (pintype "passive"))
      (node (ref "R21") (pin "2") (pinfunction "2_2") (pintype "passive"))
      (node (ref "U4") (pin "15") (pinfunction "GPIO22_15") (pintype "passive"))
    )
    (net (code "38") (name "/OI6") (class "Default")
      (node (ref "D18") (pin "4") (pinfunction "4_4") (pintype "passive"))
      (node (ref "R22") (pin "2") (pinfunction "2_2") (pintype "passive"))
      (node (ref "U4") (pin "13") (pinfunction "GPIO27_13") (pintype "passive"))
    )
    (net (code "39") (name "/OI7") (class "Default")
      (node (ref "D19") (pin "4") (pinfunction "4_4") (pintype "passive"))
      (node (ref "R23") (pin "2") (pinfunction "2_2") (pintype "passive"))
      (node (ref "U4") (pin "11") (pinfunction "GPIO17_11") (pintype "passive"))
    )
    (net (code "40") (name "/OI8") (class "Default")
      (node (ref "D20") (pin "4") (pinfunction "4_4") (pintype "passive"))
      (node (ref "R24") (pin "2") (pinfunction "2_2") (pintype "passive"))
      (node (ref "U4") (pin "7") (pinfunction "GPIO4_7") (pintype "passive"))
    )
    (net (code "41") (name "/RXD") (class "Default")
      (node (ref "J9") (pin "24") (pinfunction "24_24") (pintype "passive"))
      (node (ref "U4") (pin "10") (pinfunction "RXD_10") (pintype "passive"))
    )
    (net (code "42") (name "/Rele1") (class "Default")
      (node (ref "R13") (pin "1") (pinfunction "1_1") (pintype "passive"))
      (node (ref "U4") (pin "40") (pinfunction "GPIO21_40") (pintype "passive"))
    )
    (net (code "43") (name "/Rele2") (class "Default")
      (node (ref "R14") (pin "1") (pinfunction "1_1") (pintype "passive"))
      (node (ref "U4") (pin "38") (pinfunction "GPIO20_38") (pintype "passive"))
    )
    (net (code "44") (name "/Rele3") (class "Default")
      (node (ref "R15") (pin "1") (pinfunction "1_1") (pintype "passive"))
      (node (ref "U4") (pin "36") (pinfunction "GPIO16_36") (pintype "passive"))
    )
    (net (code "45") (name "/Rele4") (class "Default")
      (node (ref "R16") (pin "1") (pinfunction "1_1") (pintype "passive"))
      (node (ref "U4") (pin "32") (pinfunction "GPIO12_32") (pintype "passive"))
    )
    (net (code "46") (name "/SCL") (class "Default")
      (node (ref "J9") (pin "12") (pinfunction "12_12") (pintype "passive"))
      (node (ref "U4") (pin "5") (pinfunction "SCL_5") (pintype "passive"))
    )
    (net (code "47") (name "/SCLK") (class "Default")
      (node (ref "J9") (pin "15") (pinfunction "15_15") (pintype "passive"))
      (node (ref "U4") (pin "23") (pinfunction "SCLK_23") (pintype "passive"))
    )
    (net (code "48") (name "/SDA") (class "Default")
      (node (ref "J9") (pin "11") (pinfunction "11_11") (pintype "passive"))
      (node (ref "U4") (pin "3") (pinfunction "SDA_3") (pintype "passive"))
    )
    (net (code "49") (name "/TXD") (class "Default")
      (node (ref "J9") (pin "23") (pinfunction "23_23") (pintype "passive"))
      (node (ref "U4") (pin "8") (pinfunction "TXD_8") (pintype "passive"))
    )
    (net (code "50") (name "3V3") (class "Default")
      (node (ref "J9") (pin "20") (pinfunction "20_20") (pintype "passive"))
      (node (ref "J9") (pin "8") (pinfunction "8_8") (pintype "passive"))
      (node (ref "R17") (pin "1") (pinfunction "1_1") (pintype "passive"))
      (node (ref "R18") (pin "1") (pinfunction "1_1") (pintype "passive"))
      (node (ref "R19") (pin "1") (pinfunction "1_1") (pintype "passive"))
      (node (ref "R20") (pin "1") (pinfunction "1_1") (pintype "passive"))
      (node (ref "R21") (pin "1") (pinfunction "1_1") (pintype "passive"))
      (node (ref "R22") (pin "1") (pinfunction "1_1") (pintype "passive"))
      (node (ref "R23") (pin "1") (pinfunction "1_1") (pintype "passive"))
      (node (ref "R24") (pin "1") (pinfunction "1_1") (pintype "passive"))
      (node (ref "U4") (pin "1") (pinfunction "3.3V_1") (pintype "passive"))
      (node (ref "U4") (pin "17") (pinfunction "3.3V_17") (pintype "passive"))
    )
    (net (code "51") (name "GND") (class "Default")
      (node (ref "C1") (pin "1") (pinfunction "1_1") (pintype "passive"))
      (node (ref "C11") (pin "1") (pinfunction "1_1") (pintype "passive"))
      (node (ref "C12") (pin "2") (pinfunction "2_2") (pintype "passive"))
      (node (ref "C13") (pin "2") (pinfunction "2_2") (pintype "passive"))
      (node (ref "C2") (pin "1") (pinfunction "1_1") (pintype "passive"))
      (node (ref "C3") (pin "2") (pinfunction "2_2") (pintype "passive"))
      (node (ref "C4") (pin "2") (pinfunction "2_2") (pintype "passive"))
      (node (ref "C7") (pin "1") (pinfunction "1_1") (pintype "passive"))
      (node (ref "C8") (pin "1") (pinfunction "1_1") (pintype "passive"))
      (node (ref "C9") (pin "1") (pinfunction "1_1") (pintype "passive"))
      (node (ref "D13") (pin "2") (pinfunction "2_2") (pintype "passive"))
      (node (ref "D13") (pin "3") (pinfunction "3_3") (pintype "passive"))
      (node (ref "D14") (pin "2") (pinfunction "2_2") (pintype "passive"))
      (node (ref "D14") (pin "3") (pinfunction "3_3") (pintype "passive"))
      (node (ref "D15") (pin "2") (pinfunction "2_2") (pintype "passive"))
      (node (ref "D15") (pin "3") (pinfunction "3_3") (pintype "passive"))
      (node (ref "D16") (pin "2") (pinfunction "2_2") (pintype "passive"))
      (node (ref "D16") (pin "3") (pinfunction "3_3") (pintype "passive"))
      (node (ref "D17") (pin "2") (pinfunction "2_2") (pintype "passive"))
      (node (ref "D17") (pin "3") (pinfunction "3_3") (pintype "passive"))
      (node (ref "D18") (pin "2") (pinfunction "2_2") (pintype "passive"))
      (node (ref "D18") (pin "3") (pinfunction "3_3") (pintype "passive"))
      (node (ref "D19") (pin "2") (pinfunction "2_2") (pintype "passive"))
      (node (ref "D19") (pin "3") (pinfunction "3_3") (pintype "passive"))
      (node (ref "D20") (pin "2") (pinfunction "2_2") (pintype "passive"))
      (node (ref "D20") (pin "3") (pinfunction "3_3") (pintype "passive"))
      (node (ref "J8") (pin "1") (pinfunction "1_1") (pintype "passive"))
      (node (ref "J8") (pin "2") (pinfunction "2_2") (pintype "passive"))
      (node (ref "J8") (pin "3") (pinfunction "3_3") (pintype "passive"))
      (node (ref "J9") (pin "10") (pinfunction "10_10") (pintype "passive"))
      (node (ref "J9") (pin "18") (pinfunction "18_18") (pintype "passive"))
      (node (ref "J9") (pin "22") (pinfunction "22_22") (pintype "passive"))
      (node (ref "J9") (pin "6") (pinfunction "6_6") (pintype "passive"))
      (node (ref "Q1") (pin "2") (pinfunction "E_2") (pintype "passive"))
      (node (ref "Q2") (pin "2") (pinfunction "E_2") (pintype "passive"))
      (node (ref "Q3") (pin "2") (pinfunction "E_2") (pintype "passive"))
      (node (ref "Q4") (pin "2") (pinfunction "E_2") (pintype "passive"))
      (node (ref "Q5") (pin "2") (pinfunction "E_2") (pintype "passive"))
      (node (ref "Q6") (pin "2") (pinfunction "E_2") (pintype "passive"))
      (node (ref "Q7") (pin "2") (pinfunction "E_2") (pintype "passive"))
      (node (ref "Q8") (pin "2") (pinfunction "E_2") (pintype "passive"))
      (node (ref "R25") (pin "1") (pinfunction "1_1") (pintype "passive"))
      (node (ref "R26") (pin "1") (pinfunction "1_1") (pintype "passive"))
      (node (ref "R27") (pin "1") (pinfunction "1_1") (pintype "passive"))
      (node (ref "R28") (pin "1") (pinfunction "1_1") (pintype "passive"))
      (node (ref "R38") (pin "1") (pinfunction "1_1") (pintype "passive"))
      (node (ref "R40") (pin "1") (pinfunction "1_1") (pintype "passive"))
      (node (ref "U1") (pin "1") (pinfunction "GND_1") (pintype "power_in"))
      (node (ref "U2") (pin "4") (pinfunction "GND_4") (pintype "power_in"))
      (node (ref "U4") (pin "14") (pinfunction "GND_14") (pintype "passive"))
      (node (ref "U4") (pin "20") (pinfunction "GND_20") (pintype "passive"))
      (node (ref "U4") (pin "25") (pinfunction "GND_25") (pintype "passive"))
      (node (ref "U4") (pin "30") (pinfunction "GND_30") (pintype "passive"))
      (node (ref "U4") (pin "34") (pinfunction "GND_34") (pintype "passive"))
      (node (ref "U4") (pin "39") (pinfunction "GND_39") (pintype "passive"))
      (node (ref "U4") (pin "6") (pinfunction "GND_6") (pintype "passive"))
      (node (ref "U4") (pin "9") (pinfunction "GND_9") (pintype "passive"))
    )
    (net (code "52") (name "Net-(D1-Pad2)") (class "Default")
      (node (ref "D1") (pin "2") (pinfunction "2_2") (pintype "passive"))
      (node (ref "R1") (pin "1") (pinfunction "1_1") (pintype "passive"))
    )
    (net (code "53") (name "Net-(D1-Pad3)") (class "Default")
      (node (ref "D1") (pin "3") (pinfunction "3_3") (pintype "passive"))
      (node (ref "R9") (pin "1") (pinfunction "1_1") (pintype "passive"))
    )
    (net (code "54") (name "Net-(D2-Pad2)") (class "Default")
      (node (ref "D2") (pin "2") (pinfunction "2_2") (pintype "passive"))
      (node (ref "R2") (pin "1") (pinfunction "1_1") (pintype "passive"))
    )
    (net (code "55") (name "Net-(D2-Pad3)") (class "Default")
      (node (ref "D2") (pin "3") (pinfunction "3_3") (pintype "passive"))
      (node (ref "R10") (pin "1") (pinfunction "1_1") (pintype "passive"))
    )
    (net (code "56") (name "Net-(D3-Pad2)") (class "Default")
      (node (ref "D3") (pin "2") (pinfunction "2_2") (pintype "passive"))
      (node (ref "R3") (pin "1") (pinfunction "1_1") (pintype "passive"))
    )
    (net (code "57") (name "Net-(D3-Pad3)") (class "Default")
      (node (ref "D3") (pin "3") (pinfunction "3_3") (pintype "passive"))
      (node (ref "R11") (pin "1") (pinfunction "1_1") (pintype "passive"))
    )
    (net (code "58") (name "Net-(D4-Pad2)") (class "Default")
      (node (ref "D4") (pin "2") (pinfunction "2_2") (pintype "passive"))
      (node (ref "R4") (pin "1") (pinfunction "1_1") (pintype "passive"))
    )
    (net (code "59") (name "Net-(D4-Pad3)") (class "Default")
      (node (ref "D4") (pin "3") (pinfunction "3_3") (pintype "passive"))
      (node (ref "R12") (pin "1") (pinfunction "1_1") (pintype "passive"))
    )
    (net (code "60") (name "Net-(D5-Pad2)") (class "Default")
      (node (ref "D5") (pin "2") (pinfunction "2_2") (pintype "passive"))
      (node (ref "R5") (pin "2") (pinfunction "2_2") (pintype "passive"))
    )
    (net (code "61") (name "Net-(D6-Pad2)") (class "Default")
      (node (ref "D6") (pin "2") (pinfunction "2_2") (pintype "passive"))
      (node (ref "R6") (pin "2") (pinfunction "2_2") (pintype "passive"))
    )
    (net (code "62") (name "Net-(D7-Pad2)") (class "Default")
      (node (ref "D7") (pin "2") (pinfunction "2_2") (pintype "passive"))
      (node (ref "R7") (pin "2") (pinfunction "2_2") (pintype "passive"))
    )
    (net (code "63") (name "Net-(D8-Pad2)") (class "Default")
      (node (ref "D8") (pin "2") (pinfunction "2_2") (pintype "passive"))
      (node (ref "R8") (pin "2") (pinfunction "2_2") (pintype "passive"))
    )
    (net (code "64") (name "Net-(D13-Pad1)") (class "Default")
      (node (ref "D13") (pin "1") (pinfunction "1_1") (pintype "passive"))
      (node (ref "R29") (pin "1") (pinfunction "1_1") (pintype "passive"))
    )
    (net (code "65") (name "Net-(D14-Pad1)") (class "Default")
      (node (ref "D14") (pin "1") (pinfunction "1_1") (pintype "passive"))
      (node (ref "R30") (pin "1") (pinfunction "1_1") (pintype "passive"))
    )
    (net (code "66") (name "Net-(D15-Pad1)") (class "Default")
      (node (ref "D15") (pin "1") (pinfunction "1_1") (pintype "passive"))
      (node (ref "R31") (pin "1") (pinfunction "1_1") (pintype "passive"))
    )
    (net (code "67") (name "Net-(D16-Pad1)") (class "Default")
      (node (ref "D16") (pin "1") (pinfunction "1_1") (pintype "passive"))
      (node (ref "R32") (pin "1") (pinfunction "1_1") (pintype "passive"))
    )
    (net (code "68") (name "Net-(D17-Pad1)") (class "Default")
      (node (ref "D17") (pin "1") (pinfunction "1_1") (pintype "passive"))
      (node (ref "R33") (pin "1") (pinfunction "1_1") (pintype "passive"))
    )
    (net (code "69") (name "Net-(D18-Pad1)") (class "Default")
      (node (ref "D18") (pin "1") (pinfunction "1_1") (pintype "passive"))
      (node (ref "R34") (pin "1") (pinfunction "1_1") (pintype "passive"))
    )
    (net (code "70") (name "Net-(D19-Pad1)") (class "Default")
      (node (ref "D19") (pin "1") (pinfunction "1_1") (pintype "passive"))
      (node (ref "R35") (pin "1") (pinfunction "1_1") (pintype "passive"))
    )
    (net (code "71") (name "Net-(D20-Pad1)") (class "Default")
      (node (ref "D20") (pin "1") (pinfunction "1_1") (pintype "passive"))
      (node (ref "R36") (pin "1") (pinfunction "1_1") (pintype "passive"))
    )
    (net (code "72") (name "Net-(Q1-B)") (class "Default")
      (node (ref "Q1") (pin "1") (pinfunction "B_1") (pintype "passive"))
      (node (ref "R13") (pin "2") (pinfunction "2_2") (pintype "passive"))
      (node (ref "R25") (pin "2") (pinfunction "2_2") (pintype "passive"))
    )
    (net (code "73") (name "Net-(Q1-C)") (class "Default")
      (node (ref "Q1") (pin "3") (pinfunction "C_3") (pintype "passive"))
      (node (ref "R1") (pin "2") (pinfunction "2_2") (pintype "passive"))
    )
    (net (code "74") (name "Net-(Q2-B)") (class "Default")
      (node (ref "Q2") (pin "1") (pinfunction "B_1") (pintype "passive"))
      (node (ref "R14") (pin "2") (pinfunction "2_2") (pintype "passive"))
      (node (ref "R26") (pin "2") (pinfunction "2_2") (pintype "passive"))
    )
    (net (code "75") (name "Net-(Q2-C)") (class "Default")
      (node (ref "Q2") (pin "3") (pinfunction "C_3") (pintype "passive"))
      (node (ref "R2") (pin "2") (pinfunction "2_2") (pintype "passive"))
    )
    (net (code "76") (name "Net-(Q3-B)") (class "Default")
      (node (ref "Q3") (pin "1") (pinfunction "B_1") (pintype "passive"))
      (node (ref "R15") (pin "2") (pinfunction "2_2") (pintype "passive"))
      (node (ref "R27") (pin "2") (pinfunction "2_2") (pintype "passive"))
    )
    (net (code "77") (name "Net-(Q3-C)") (class "Default")
      (node (ref "Q3") (pin "3") (pinfunction "C_3") (pintype "passive"))
      (node (ref "R3") (pin "2") (pinfunction "2_2") (pintype "passive"))
    )
    (net (code "78") (name "Net-(Q4-B)") (class "Default")
      (node (ref "Q4") (pin "1") (pinfunction "B_1") (pintype "passive"))
      (node (ref "R16") (pin "2") (pinfunction "2_2") (pintype "passive"))
      (node (ref "R28") (pin "2") (pinfunction "2_2") (pintype "passive"))
    )
    (net (code "79") (name "Net-(Q4-C)") (class "Default")
      (node (ref "Q4") (pin "3") (pinfunction "C_3") (pintype "passive"))
      (node (ref "R4") (pin "2") (pinfunction "2_2") (pintype "passive"))
    )
    (net (code "80") (name "Net-(Q5-B)") (class "Default")
      (node (ref "Q5") (pin "1") (pinfunction "B_1") (pintype "passive"))
      (node (ref "R9") (pin "2") (pinfunction "2_2") (pintype "passive"))
    )
    (net (code "81") (name "Net-(Q5-C)") (class "Default")
      (node (ref "D9") (pin "1") (pinfunction "1_1") (pintype "passive"))
      (node (ref "K1") (pin "A2") (pinfunction "A2_A2") (pintype "passive"))
      (node (ref "Q5") (pin "3") (pinfunction "C_3") (pintype "passive"))
      (node (ref "R5") (pin "1") (pinfunction "1_1") (pintype "passive"))
    )
    (net (code "82") (name "Net-(Q6-B)") (class "Default")
      (node (ref "Q6") (pin "1") (pinfunction "B_1") (pintype "passive"))
      (node (ref "R10") (pin "2") (pinfunction "2_2") (pintype "passive"))
    )
    (net (code "83") (name "Net-(Q6-C)") (class "Default")
      (node (ref "D10") (pin "1") (pinfunction "1_1") (pintype "passive"))
      (node (ref "K2") (pin "A2") (pinfunction "A2_A2") (pintype "passive"))
      (node (ref "Q6") (pin "3") (pinfunction "C_3") (pintype "passive"))
      (node (ref "R6") (pin "1") (pinfunction "1_1") (pintype "passive"))
    )
    (net (code "84") (name "Net-(Q7-B)") (class "Default")
      (node (ref "Q7") (pin "1") (pinfunction "B_1") (pintype "passive"))
      (node (ref "R11") (pin "2") (pinfunction "2_2") (pintype "passive"))
    )
    (net (code "85") (name "Net-(Q7-C)") (class "Default")
      (node (ref "D11") (pin "1") (pinfunction "1_1") (pintype "passive"))
      (node (ref "K3") (pin "A2") (pinfunction "A2_A2") (pintype "passive"))
      (node (ref "Q7") (pin "3") (pinfunction "C_3") (pintype "passive"))
      (node (ref "R7") (pin "1") (pinfunction "1_1") (pintype "passive"))
    )
    (net (code "86") (name "Net-(Q8-B)") (class "Default")
      (node (ref "Q8") (pin "1") (pinfunction "B_1") (pintype "passive"))
      (node (ref "R12") (pin "2") (pinfunction "2_2") (pintype "passive"))
    )
    (net (code "87") (name "Net-(Q8-C)") (class "Default")
      (node (ref "D12") (pin "1") (pinfunction "1_1") (pintype "passive"))
      (node (ref "K4") (pin "A2") (pinfunction "A2_A2") (pintype "passive"))
      (node (ref "Q8") (pin "3") (pinfunction "C_3") (pintype "passive"))
      (node (ref "R8") (pin "1") (pinfunction "1_1") (pintype "passive"))
    )
    (net (code "88") (name "Net-(U1-SW)") (class "Default")
      (node (ref "C5") (pin "1") (pinfunction "1_1") (pintype "passive"))
      (node (ref "L1") (pin "1") (pinfunction "1_1") (pintype "passive"))
      (node (ref "U1") (pin "2") (pinfunction "SW_2") (pintype "passive"))
    )
    (net (code "89") (name "Net-(U1-VBST)") (class "Default")
      (node (ref "C5") (pin "2") (pinfunction "2_2") (pintype "passive"))
      (node (ref "U1") (pin "6") (pinfunction "VBST_6") (pintype "passive"))
    )
    (net (code "90") (name "Net-(U1-VFB)") (class "Default")
      (node (ref "R37") (pin "1") (pinfunction "1_1") (pintype "passive"))
      (node (ref "R38") (pin "2") (pinfunction "2_2") (pintype "passive"))
      (node (ref "U1") (pin "4") (pinfunction "VFB_4") (pintype "passive"))
    )
    (net (code "91") (name "Net-(U2-BST)") (class "Default")
      (node (ref "C6") (pin "1") (pinfunction "1_1") (pintype "passive"))
      (node (ref "U2") (pin "6") (pinfunction "BST_6") (pintype "passive"))
    )
    (net (code "92") (name "Net-(U2-FB)") (class "Default")
      (node (ref "C10") (pin "1") (pinfunction "1_1") (pintype "passive"))
      (node (ref "R39") (pin "1") (pinfunction "1_1") (pintype "passive"))
      (node (ref "R40") (pin "2") (pinfunction "2_2") (pintype "passive"))
      (node (ref "U2") (pin "8") (pinfunction "FB_8") (pintype "passive"))
    )
    (net (code "93") (name "Net-(U2-SS)") (class "Default")
      (node (ref "C11") (pin "2") (pinfunction "2_2") (pintype "passive"))
      (node (ref "U2") (pin "7") (pinfunction "SS_7") (pintype "passive"))
    )
    (net (code "94") (name "Net-(U2-SW)") (class "Default")
      (node (ref "C6") (pin "2") (pinfunction "2_2") (pintype "passive"))
      (node (ref "L2") (pin "1") (pinfunction "1_1") (pintype "passive"))
      (node (ref "U2") (pin "5") (pinfunction "SW_5") (pintype "passive"))
    )
    (net (code "95") (name "unconnected-(U2-EN-Pad2)") (class "Default")
      (node (ref "U2") (pin "2") (pinfunction "EN_2") (pintype "passive+no_connect"))
    )
    (net (code "96") (name "unconnected-(U2-RT-Pad1)") (class "Default")
      (node (ref "U2") (pin "1") (pinfunction "RT_1") (pintype "passive+no_connect"))
    )
    (net (code "97") (name "unconnected-(U4-DNC-Pad27)") (class "Default")
      (node (ref "U4") (pin "27") (pinfunction "DNC_27") (pintype "passive+no_connect"))
    )
    (net (code "98") (name "unconnected-(U4-DNC-Pad28)") (class "Default")
      (node (ref "U4") (pin "28") (pinfunction "DNC_28") (pintype "passive+no_connect"))
    )
  )
)
